# main.net
KiCad netlist of a schematic drawn in EAGLE
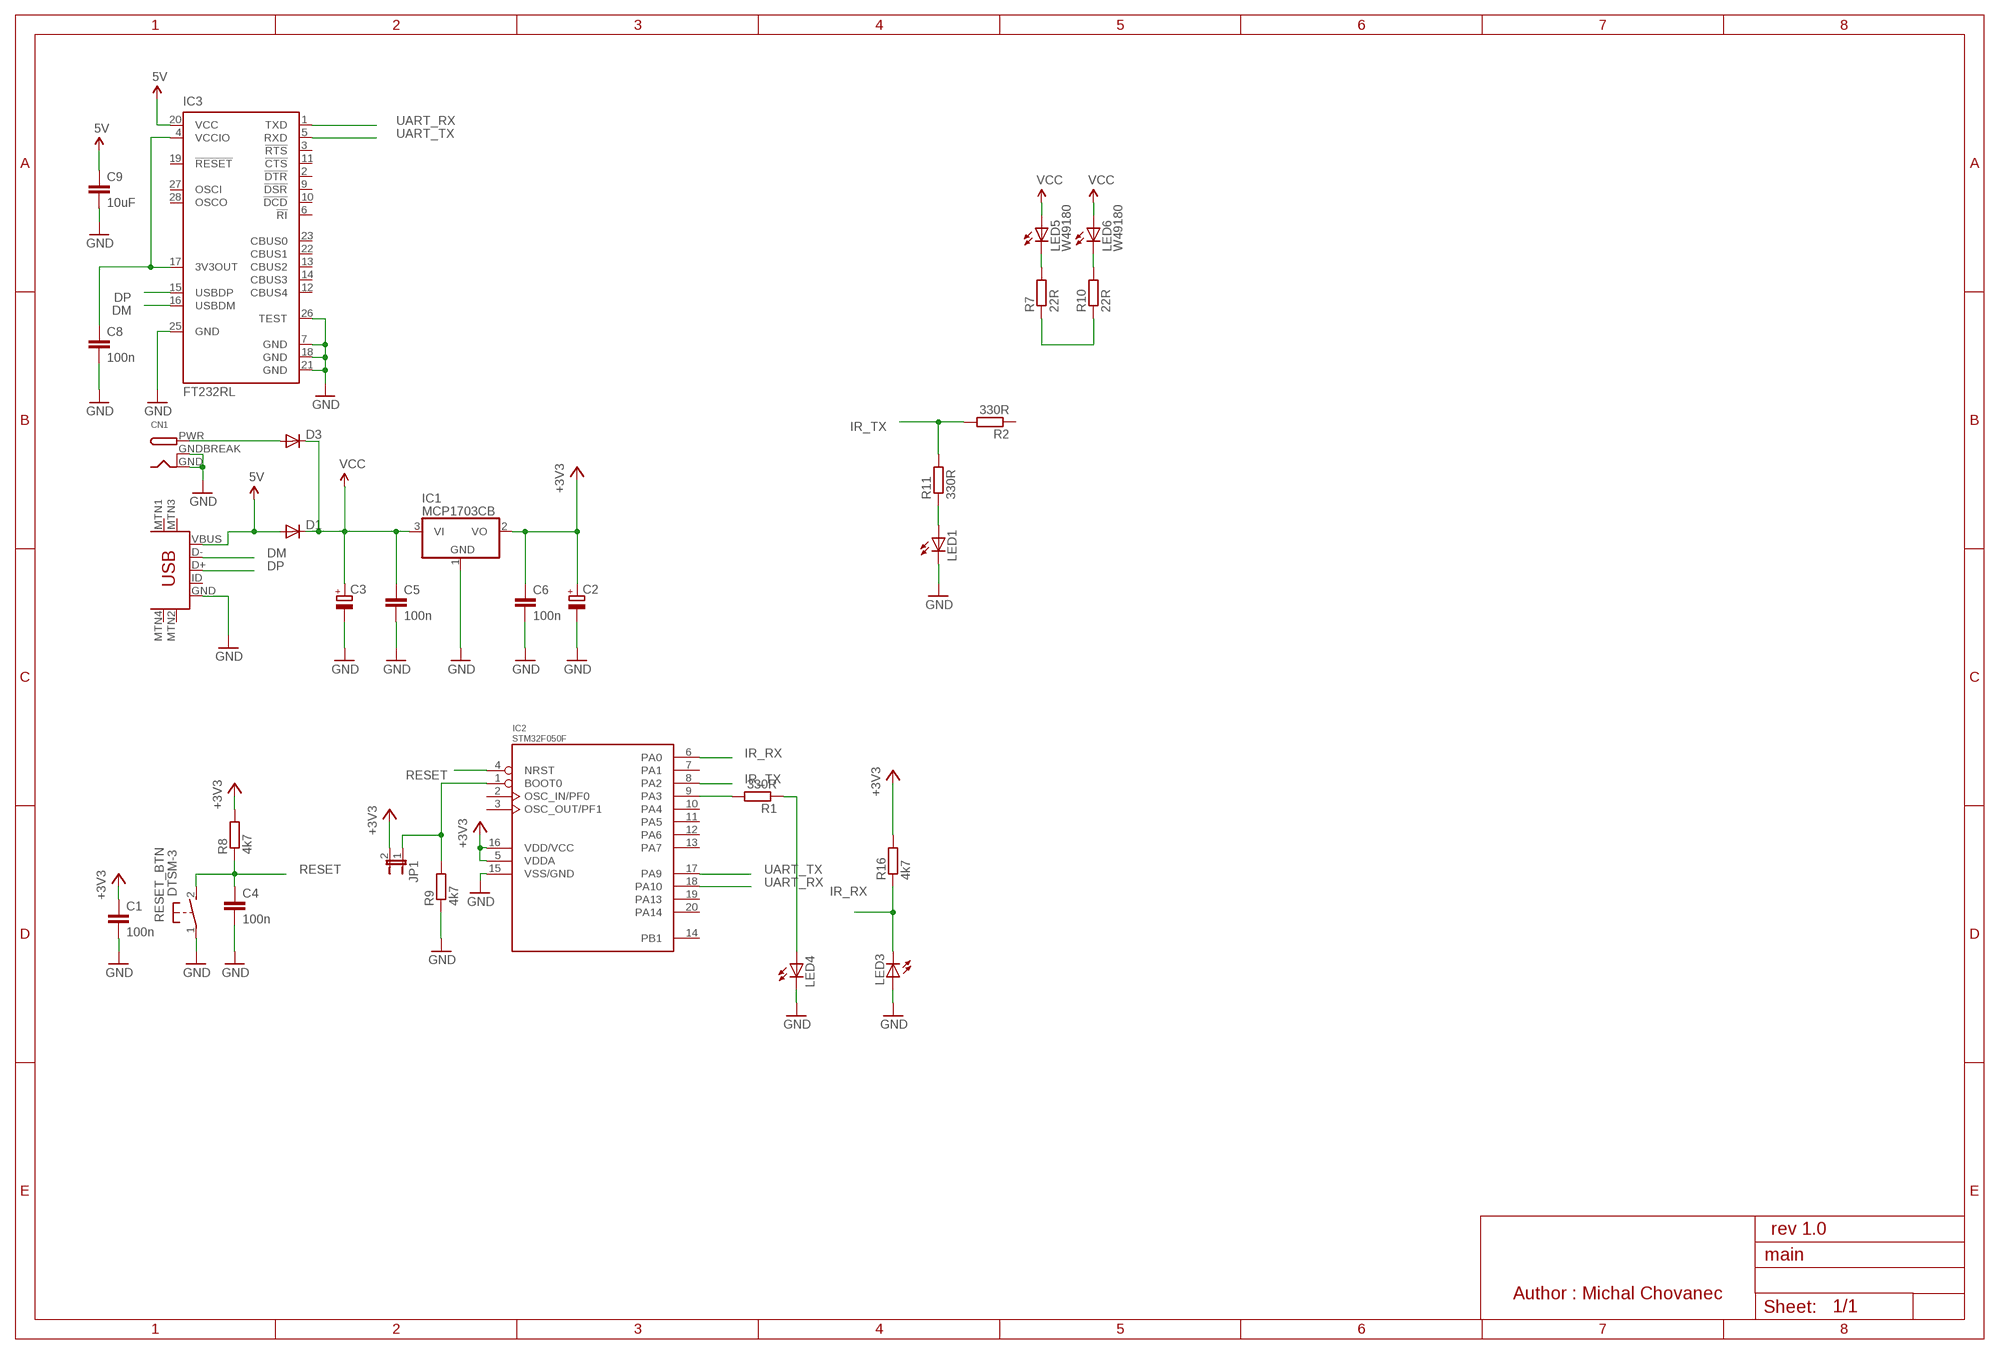
[diagram p0: schematic, sheet 1]

(export (version "E")
  (design (tool "Eeschema 10.0.6"))
  (components
    (comp (ref "C1")
      (value "100n")
      (footprint "eagle-import:C0805")
      (libsource (lib "eagle-import") (part "C-EUC0805"))
    )
    (comp (ref "C2")
      (value "CPOL-EU153CLV-0405")
      (footprint "eagle-import:153CLV-0405")
      (libsource (lib "eagle-import") (part "resistor_CPOL-EU153CLV-0405"))
    )
    (comp (ref "C3")
      (value "CPOL-EU150CLZ-1010")
      (footprint "eagle-import:150CLZ-1010")
      (libsource (lib "eagle-import") (part "CPOL-EU150CLZ-1010"))
    )
    (comp (ref "C4")
      (value "100n")
      (footprint "eagle-import:C0805")
      (libsource (lib "eagle-import") (part "C-EUC0805"))
    )
    (comp (ref "C5")
      (value "100n")
      (footprint "eagle-import:C0805")
      (libsource (lib "eagle-import") (part "C-EUC0805"))
    )
    (comp (ref "C6")
      (value "100n")
      (footprint "eagle-import:C0805")
      (libsource (lib "eagle-import") (part "C-EUC0805"))
    )
    (comp (ref "C8")
      (value "100n")
      (footprint "eagle-import:C0805")
      (libsource (lib "eagle-import") (part "C-EUC0805"))
    )
    (comp (ref "C9")
      (value "10uF")
      (footprint "eagle-import:C0805")
      (libsource (lib "eagle-import") (part "C-EUC0805"))
    )
    (comp (ref "CN1")
      (value "DCBARRELPTH")
      (footprint "eagle-import:DCJACK_2MM_PTH")
      (libsource (lib "eagle-import") (part "DCBARRELPTH"))
    )
    (comp (ref "D1")
      (value "DIODE-DO-214AC")
      (footprint "eagle-import:DO-214AC")
      (libsource (lib "eagle-import") (part "DIODE-DO-214AC"))
    )
    (comp (ref "D3")
      (value "DIODE-DO-214AC")
      (footprint "eagle-import:DO-214AC")
      (libsource (lib "eagle-import") (part "DIODE-DO-214AC"))
    )
    (comp (ref "IC1")
      (value "MCP1703CB")
      (footprint "eagle-import:SOT23")
      (libsource (lib "eagle-import") (part "MCP1703CB"))
    )
    (comp (ref "IC2")
      (value "STM32F050F")
      (footprint "eagle-import:TSSOP20")
      (libsource (lib "eagle-import") (part "STM32F050F"))
    )
    (comp (ref "IC3")
      (value "FT232RL")
      (footprint "eagle-import:SSOP28")
      (libsource (lib "eagle-import") (part "FT232RL"))
    )
    (comp (ref "JP1")
      (value "JP1E")
      (footprint "eagle-import:JP1")
      (libsource (lib "eagle-import") (part "JP1E"))
    )
    (comp (ref "LED1")
      (value "LEDCHIPLED_1206")
      (footprint "eagle-import:CHIPLED_1206")
      (libsource (lib "eagle-import") (part "LEDCHIPLED_1206"))
    )
    (comp (ref "LED3")
      (value "LEDCHIPLED_1206")
      (footprint "eagle-import:CHIPLED_1206")
      (libsource (lib "eagle-import") (part "LEDCHIPLED_1206"))
    )
    (comp (ref "LED4")
      (value "LEDCHIPLED_1206")
      (footprint "eagle-import:CHIPLED_1206")
      (libsource (lib "eagle-import") (part "LEDCHIPLED_1206"))
    )
    (comp (ref "LED5")
      (value "W49180")
      (footprint "eagle-import:Z-POWER-LED-DOME-TYPE")
      (libsource (lib "eagle-import") (part "W49180"))
    )
    (comp (ref "LED6")
      (value "W49180")
      (footprint "eagle-import:Z-POWER-LED-DOME-TYPE")
      (libsource (lib "eagle-import") (part "W49180"))
    )
    (comp (ref "R1")
      (value "330R")
      (footprint "eagle-import:M0805")
      (libsource (lib "eagle-import") (part "R-EU_M0805"))
    )
    (comp (ref "R2")
      (value "330R")
      (footprint "eagle-import:M0805")
      (libsource (lib "eagle-import") (part "R-EU_M0805"))
    )
    (comp (ref "R7")
      (value "22R")
      (footprint "eagle-import:M0805")
      (libsource (lib "eagle-import") (part "R-EU_M0805"))
    )
    (comp (ref "R8")
      (value "4k7")
      (footprint "eagle-import:M0805")
      (libsource (lib "eagle-import") (part "R-EU_M0805"))
    )
    (comp (ref "R9")
      (value "4k7")
      (footprint "eagle-import:M0805")
      (libsource (lib "eagle-import") (part "R-EU_M0805"))
    )
    (comp (ref "R10")
      (value "22R")
      (footprint "eagle-import:M0805")
      (libsource (lib "eagle-import") (part "R-EU_M0805"))
    )
    (comp (ref "R11")
      (value "330R")
      (footprint "eagle-import:M0805")
      (libsource (lib "eagle-import") (part "R-EU_M0805"))
    )
    (comp (ref "R16")
      (value "4k7")
      (footprint "eagle-import:M0805")
      (libsource (lib "eagle-import") (part "R-EU_M0805"))
    )
    (comp (ref "RESET_BTN")
      (value "DTSM-3")
      (footprint "eagle-import:DTSM-3")
      (libsource (lib "eagle-import") (part "DTSM-3"))
    )
    (comp (ref "U$1")
      (value "USB-MINIB-5PIN")
      (footprint "eagle-import:USB-MINIB")
      (libsource (lib "eagle-import") (part "USB-MINIB-5PIN"))
    )
  )
  (nets
    (net (code "1") (name "+3V3") (class "Default")
      (node (ref "C1") (pin "1") (pinfunction "1_1") (pintype "passive"))
      (node (ref "C2") (pin "+") (pinfunction "+_+") (pintype "passive"))
      (node (ref "C6") (pin "1") (pinfunction "1_1") (pintype "passive"))
      (node (ref "IC1") (pin "2") (pinfunction "VO_2") (pintype "passive"))
      (node (ref "IC2") (pin "16") (pinfunction "VDD/VCC_16") (pintype "power_in"))
      (node (ref "IC2") (pin "5") (pinfunction "VDDA_5") (pintype "power_in"))
      (node (ref "JP1") (pin "2") (pinfunction "2_2") (pintype "passive"))
      (node (ref "R16") (pin "2") (pinfunction "2_2") (pintype "passive"))
      (node (ref "R8") (pin "2") (pinfunction "2_2") (pintype "passive"))
    )
    (net (code "2") (name "/DM") (class "Default")
      (node (ref "IC3") (pin "16") (pinfunction "USBDM_16") (pintype "bidirectional"))
      (node (ref "U$1") (pin "D-") (pinfunction "D-_D-") (pintype "bidirectional"))
    )
    (net (code "3") (name "/DP") (class "Default")
      (node (ref "IC3") (pin "15") (pinfunction "USBDP_15") (pintype "bidirectional"))
      (node (ref "U$1") (pin "D+") (pinfunction "D+_D+") (pintype "bidirectional"))
    )
    (net (code "4") (name "/IR_RX") (class "Default")
      (node (ref "IC2") (pin "6") (pinfunction "PA0_6") (pintype "bidirectional"))
      (node (ref "LED3") (pin "C") (pinfunction "C_C") (pintype "passive"))
      (node (ref "R16") (pin "1") (pinfunction "1_1") (pintype "passive"))
    )
    (net (code "5") (name "/IR_TX") (class "Default")
      (node (ref "IC2") (pin "8") (pinfunction "PA2_8") (pintype "bidirectional"))
      (node (ref "R11") (pin "2") (pinfunction "2_2") (pintype "passive"))
      (node (ref "R2") (pin "2") (pinfunction "2_2") (pintype "passive"))
    )
    (net (code "6") (name "/RESET") (class "Default")
      (node (ref "C4") (pin "1") (pinfunction "1_1") (pintype "passive"))
      (node (ref "IC2") (pin "4") (pinfunction "NRST_4") (pintype "bidirectional"))
      (node (ref "R8") (pin "1") (pinfunction "1_1") (pintype "passive"))
      (node (ref "RESET_BTN") (pin "2") (pinfunction "2_2") (pintype "passive"))
    )
    (net (code "7") (name "/UART_RX") (class "Default")
      (node (ref "IC2") (pin "18") (pinfunction "PA10_18") (pintype "bidirectional"))
      (node (ref "IC3") (pin "1") (pinfunction "TXD_1") (pintype "output"))
    )
    (net (code "8") (name "/UART_TX") (class "Default")
      (node (ref "IC2") (pin "17") (pinfunction "PA9_17") (pintype "bidirectional"))
      (node (ref "IC3") (pin "5") (pinfunction "RXD_5") (pintype "input"))
    )
    (net (code "9") (name "5V") (class "Default")
      (node (ref "C9") (pin "1") (pinfunction "1_1") (pintype "passive"))
      (node (ref "D1") (pin "A") (pinfunction "A_A") (pintype "passive"))
      (node (ref "IC3") (pin "20") (pinfunction "VCC_20") (pintype "power_in"))
      (node (ref "U$1") (pin "VBUS") (pinfunction "VBUS_VBUS") (pintype "bidirectional"))
    )
    (net (code "10") (name "GND") (class "Default")
      (node (ref "C1") (pin "2") (pinfunction "2_2") (pintype "passive"))
      (node (ref "C2") (pin "-") (pinfunction "-_-") (pintype "passive"))
      (node (ref "C3") (pin "-") (pinfunction "-_-") (pintype "passive"))
      (node (ref "C4") (pin "2") (pinfunction "2_2") (pintype "passive"))
      (node (ref "C5") (pin "2") (pinfunction "2_2") (pintype "passive"))
      (node (ref "C6") (pin "2") (pinfunction "2_2") (pintype "passive"))
      (node (ref "C8") (pin "2") (pinfunction "2_2") (pintype "passive"))
      (node (ref "C9") (pin "2") (pinfunction "2_2") (pintype "passive"))
      (node (ref "CN1") (pin "GND") (pinfunction "GND_GND") (pintype "power_in"))
      (node (ref "CN1") (pin "GNDBREAK") (pinfunction "GNDBREAK_GNDBREAK") (pintype "power_in"))
      (node (ref "IC1") (pin "1") (pinfunction "GND_1") (pintype "passive"))
      (node (ref "IC2") (pin "15") (pinfunction "VSS/GND_15") (pintype "power_in"))
      (node (ref "IC3") (pin "18") (pinfunction "GND_18") (pintype "power_in"))
      (node (ref "IC3") (pin "21") (pinfunction "GND_21") (pintype "power_in"))
      (node (ref "IC3") (pin "25") (pinfunction "GND_25") (pintype "power_in"))
      (node (ref "IC3") (pin "26") (pinfunction "TEST_26") (pintype "input"))
      (node (ref "IC3") (pin "7") (pinfunction "GND_7") (pintype "power_in"))
      (node (ref "LED1") (pin "C") (pinfunction "C_C") (pintype "passive"))
      (node (ref "LED3") (pin "A") (pinfunction "A_A") (pintype "passive"))
      (node (ref "LED4") (pin "C") (pinfunction "C_C") (pintype "passive"))
      (node (ref "R9") (pin "1") (pinfunction "1_1") (pintype "passive"))
      (node (ref "RESET_BTN") (pin "1") (pinfunction "1_1") (pintype "passive"))
      (node (ref "U$1") (pin "GND") (pinfunction "GND_GND") (pintype "bidirectional"))
    )
    (net (code "11") (name "Net-(CN1-PadPWR)") (class "Default")
      (node (ref "CN1") (pin "PWR") (pinfunction "PWR_PWR") (pintype "power_in"))
      (node (ref "D3") (pin "A") (pinfunction "A_A") (pintype "passive"))
    )
    (net (code "12") (name "Net-(IC2-BOOT0)") (class "Default")
      (node (ref "IC2") (pin "1") (pinfunction "BOOT0_1") (pintype "bidirectional"))
      (node (ref "JP1") (pin "1") (pinfunction "1_1") (pintype "passive"))
      (node (ref "R9") (pin "2") (pinfunction "2_2") (pintype "passive"))
    )
    (net (code "13") (name "Net-(IC2-PA3)") (class "Default")
      (node (ref "IC2") (pin "9") (pinfunction "PA3_9") (pintype "bidirectional"))
      (node (ref "R1") (pin "2") (pinfunction "2_2") (pintype "passive"))
    )
    (net (code "14") (name "Net-(IC3-3V3OUT)") (class "Default")
      (node (ref "C8") (pin "1") (pinfunction "1_1") (pintype "passive"))
      (node (ref "IC3") (pin "17") (pinfunction "3V3OUT_17") (pintype "output"))
      (node (ref "IC3") (pin "4") (pinfunction "VCCIO_4") (pintype "power_in"))
    )
    (net (code "15") (name "Net-(LED1-PadA)") (class "Default")
      (node (ref "LED1") (pin "A") (pinfunction "A_A") (pintype "passive"))
      (node (ref "R11") (pin "1") (pinfunction "1_1") (pintype "passive"))
    )
    (net (code "16") (name "Net-(LED4-PadA)") (class "Default")
      (node (ref "LED4") (pin "A") (pinfunction "A_A") (pintype "passive"))
      (node (ref "R1") (pin "1") (pinfunction "1_1") (pintype "passive"))
    )
    (net (code "17") (name "Net-(LED5-PadC)") (class "Default")
      (node (ref "LED5") (pin "C") (pinfunction "C_C") (pintype "passive"))
      (node (ref "R7") (pin "2") (pinfunction "2_2") (pintype "passive"))
    )
    (net (code "18") (name "Net-(LED6-PadC)") (class "Default")
      (node (ref "LED6") (pin "C") (pinfunction "C_C") (pintype "passive"))
      (node (ref "R10") (pin "2") (pinfunction "2_2") (pintype "passive"))
    )
    (net (code "19") (name "Net-(R10-Pad1)") (class "Default")
      (node (ref "R10") (pin "1") (pinfunction "1_1") (pintype "passive"))
      (node (ref "R7") (pin "1") (pinfunction "1_1") (pintype "passive"))
    )
    (net (code "20") (name "VCC") (class "Default")
      (node (ref "C3") (pin "+") (pinfunction "+_+") (pintype "passive"))
      (node (ref "C5") (pin "1") (pinfunction "1_1") (pintype "passive"))
      (node (ref "D1") (pin "C") (pinfunction "C_C") (pintype "passive"))
      (node (ref "D3") (pin "C") (pinfunction "C_C") (pintype "passive"))
      (node (ref "IC1") (pin "3") (pinfunction "VI_3") (pintype "input"))
      (node (ref "LED5") (pin "A") (pinfunction "A_A") (pintype "passive"))
      (node (ref "LED6") (pin "A") (pinfunction "A_A") (pintype "passive"))
    )
    (net (code "21") (name "unconnected-(IC2-OSC_IN{slash}PF0-Pad2)") (class "Default")
      (node (ref "IC2") (pin "2") (pinfunction "OSC_IN/PF0_2") (pintype "bidirectional"))
    )
    (net (code "22") (name "unconnected-(IC2-OSC_OUT{slash}PF1-Pad3)") (class "Default")
      (node (ref "IC2") (pin "3") (pinfunction "OSC_OUT/PF1_3") (pintype "bidirectional"))
    )
    (net (code "23") (name "unconnected-(IC2-PA1-Pad7)") (class "Default")
      (node (ref "IC2") (pin "7") (pinfunction "PA1_7") (pintype "bidirectional"))
    )
    (net (code "24") (name "unconnected-(IC2-PA4-Pad10)") (class "Default")
      (node (ref "IC2") (pin "10") (pinfunction "PA4_10") (pintype "bidirectional"))
    )
    (net (code "25") (name "unconnected-(IC2-PA5-Pad11)") (class "Default")
      (node (ref "IC2") (pin "11") (pinfunction "PA5_11") (pintype "bidirectional"))
    )
    (net (code "26") (name "unconnected-(IC2-PA6-Pad12)") (class "Default")
      (node (ref "IC2") (pin "12") (pinfunction "PA6_12") (pintype "bidirectional"))
    )
    (net (code "27") (name "unconnected-(IC2-PA7-Pad13)") (class "Default")
      (node (ref "IC2") (pin "13") (pinfunction "PA7_13") (pintype "bidirectional"))
    )
    (net (code "28") (name "unconnected-(IC2-PA13-Pad19)") (class "Default")
      (node (ref "IC2") (pin "19") (pinfunction "PA13_19") (pintype "bidirectional"))
    )
    (net (code "29") (name "unconnected-(IC2-PA14-Pad20)") (class "Default")
      (node (ref "IC2") (pin "20") (pinfunction "PA14_20") (pintype "bidirectional"))
    )
    (net (code "30") (name "unconnected-(IC2-PB1-Pad14)") (class "Default")
      (node (ref "IC2") (pin "14") (pinfunction "PB1_14") (pintype "bidirectional"))
    )
    (net (code "31") (name "unconnected-(IC3-CBUS0-Pad23)") (class "Default")
      (node (ref "IC3") (pin "23") (pinfunction "CBUS0_23") (pintype "bidirectional"))
    )
    (net (code "32") (name "unconnected-(IC3-CBUS1-Pad22)") (class "Default")
      (node (ref "IC3") (pin "22") (pinfunction "CBUS1_22") (pintype "bidirectional"))
    )
    (net (code "33") (name "unconnected-(IC3-CBUS2-Pad13)") (class "Default")
      (node (ref "IC3") (pin "13") (pinfunction "CBUS2_13") (pintype "bidirectional"))
    )
    (net (code "34") (name "unconnected-(IC3-CBUS3-Pad14)") (class "Default")
      (node (ref "IC3") (pin "14") (pinfunction "CBUS3_14") (pintype "bidirectional"))
    )
    (net (code "35") (name "unconnected-(IC3-CBUS4-Pad12)") (class "Default")
      (node (ref "IC3") (pin "12") (pinfunction "CBUS4_12") (pintype "bidirectional"))
    )
    (net (code "36") (name "unconnected-(IC3-OSCI-Pad27)") (class "Default")
      (node (ref "IC3") (pin "27") (pinfunction "OSCI_27") (pintype "input"))
    )
    (net (code "37") (name "unconnected-(IC3-OSCO-Pad28)") (class "Default")
      (node (ref "IC3") (pin "28") (pinfunction "OSCO_28") (pintype "output"))
    )
    (net (code "38") (name "unconnected-(IC3-~{CTS}-Pad11)") (class "Default")
      (node (ref "IC3") (pin "11") (pinfunction "~{CTS}_11") (pintype "input"))
    )
    (net (code "39") (name "unconnected-(IC3-~{DCD}-Pad10)") (class "Default")
      (node (ref "IC3") (pin "10") (pinfunction "~{DCD}_10") (pintype "input"))
    )
    (net (code "40") (name "unconnected-(IC3-~{DSR}-Pad9)") (class "Default")
      (node (ref "IC3") (pin "9") (pinfunction "~{DSR}_9") (pintype "input"))
    )
    (net (code "41") (name "unconnected-(IC3-~{DTR}-Pad2)") (class "Default")
      (node (ref "IC3") (pin "2") (pinfunction "~{DTR}_2") (pintype "output"))
    )
    (net (code "42") (name "unconnected-(IC3-~{RESET}-Pad19)") (class "Default")
      (node (ref "IC3") (pin "19") (pinfunction "~{RESET}_19") (pintype "input"))
    )
    (net (code "43") (name "unconnected-(IC3-~{RI}-Pad6)") (class "Default")
      (node (ref "IC3") (pin "6") (pinfunction "~{RI}_6") (pintype "input"))
    )
    (net (code "44") (name "unconnected-(IC3-~{RTS}-Pad3)") (class "Default")
      (node (ref "IC3") (pin "3") (pinfunction "~{RTS}_3") (pintype "output"))
    )
    (net (code "45") (name "unconnected-(R2-Pad1)") (class "Default")
      (node (ref "R2") (pin "1") (pinfunction "1_1") (pintype "passive"))
    )
    (net (code "46") (name "unconnected-(U$1-MTN1-PadMTN3)") (class "Default")
      (node (ref "U$1") (pin "MTN3") (pinfunction "MTN1_MTN3") (pintype "bidirectional"))
    )
    (net (code "47") (name "unconnected-(U$1-MTN2-PadMTN1)") (class "Default")
      (node (ref "U$1") (pin "MTN1") (pinfunction "MTN2_MTN1") (pintype "bidirectional"))
    )
    (net (code "48") (name "unconnected-(U$1-MTN3-PadMTN2)") (class "Default")
      (node (ref "U$1") (pin "MTN2") (pinfunction "MTN3_MTN2") (pintype "bidirectional"))
    )
    (net (code "49") (name "unconnected-(U$1-PadID)") (class "Default")
      (node (ref "U$1") (pin "ID") (pinfunction "ID_ID") (pintype "bidirectional"))
    )
    (net (code "50") (name "unconnected-(U$1-PadMTN4)") (class "Default")
      (node (ref "U$1") (pin "MTN4") (pinfunction "MTN4_MTN4") (pintype "bidirectional"))
    )
  )
)
